# 3-Axis_Accelerometer.net
KiCad netlist of a schematic drawn in Altium Designer
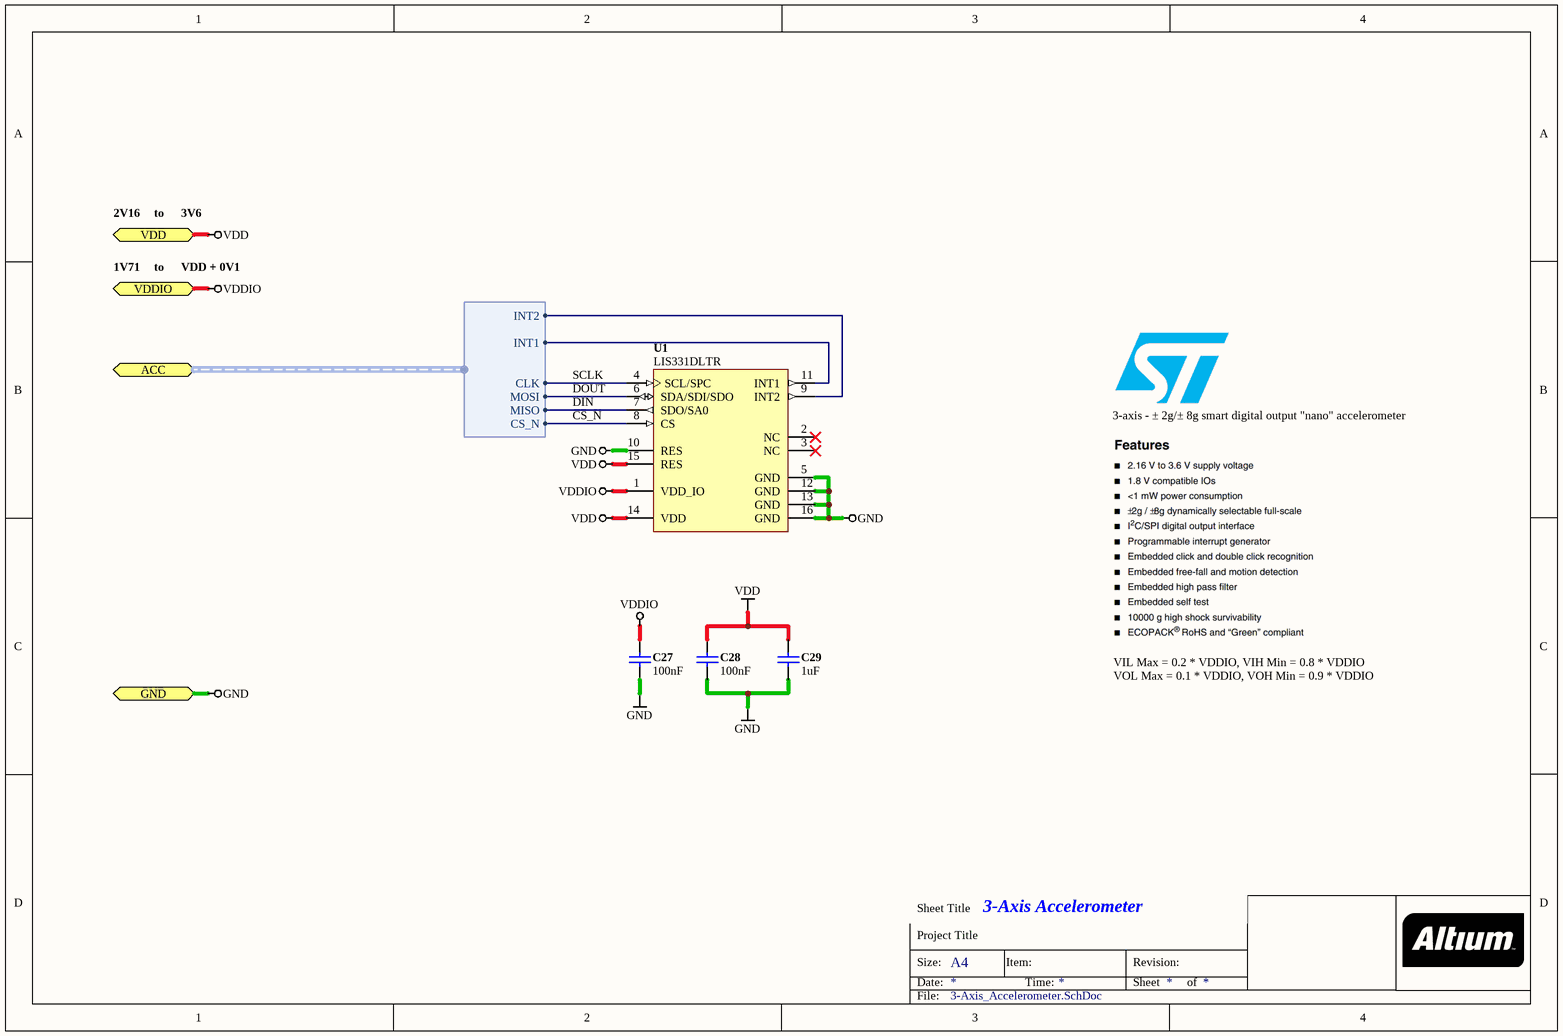
[diagram p0: 3-Axis_Accelerometer.SchDoc]

(export (version "E")
  (design (tool "Eeschema 10.0.6"))
  (components
    (comp (ref "C27")
      (value "100nF")
      (footprint "CAPC0402(1005)60_N")
      (description "CAP 100nF 16V ?0% 0402 (1005 Metric) Thickness 0.6mm SMD")
      (fields (field (name "TOLERANCE") "?0%") (field (name "Comment") "CAP 100nF 16V 0402(1005)"))
      (libsource (lib "Altium Content Vault") (part "CMP-1034-02069-1"))
    )
    (comp (ref "C28")
      (value "100nF")
      (footprint "CAPC0402(1005)60_N")
      (description "CAP 100nF 16V ?0% 0402 (1005 Metric) Thickness 0.6mm SMD")
      (fields (field (name "TOLERANCE") "?0%") (field (name "Comment") "CAP 100nF 16V 0402(1005)"))
      (libsource (lib "Altium Content Vault") (part "CMP-1034-02069-1"))
    )
    (comp (ref "C29")
      (value "1uF")
      (footprint "CAPC0402(1005)60_N")
      (description "CAP 1uF 16V ?0% 0402 (1005 Metric) Thickness 0.6mm SMD")
      (fields (field (name "TOLERANCE") "?0%") (field (name "Comment") "CAP 1uF 16V 0402(1005)"))
      (libsource (lib "Altium Content Vault") (part "CMP-1034-02119-1"))
    )
    (comp (ref "U1")
      (value "LIS331DLTR")
      (footprint "LGA16-3X3X1_L")
      (fields (field (name "MANUFACTURER") "STMicroelectronics"))
      (libsource (lib "Altium Content Vault") (part "CMP-0234-00061-2"))
    )
  )
  (nets
    (net (code "2") (name "/CS_N") (class "Default")
      (node (ref "U1") (pin "8") (pinfunction "CS_8") (pintype "input"))
    )
    (net (code "3") (name "/DIN") (class "Default")
      (node (ref "U1") (pin "7") (pinfunction "SDO/SA0_7") (pintype "output"))
    )
    (net (code "4") (name "/DOUT") (class "Default")
      (node (ref "U1") (pin "6") (pinfunction "SDA/SDI/SDO_6") (pintype "bidirectional"))
    )
    (net (code "5") (name "/INT1") (class "Default")
      (node (ref "U1") (pin "11") (pinfunction "INT1_11") (pintype "output"))
    )
    (net (code "6") (name "/INT2") (class "Default")
      (node (ref "U1") (pin "9") (pinfunction "INT2_9") (pintype "output"))
    )
    (net (code "7") (name "/SCLK") (class "Default")
      (node (ref "U1") (pin "4") (pinfunction "SCL/SPC_4") (pintype "input"))
    )
    (net (code "9") (name "GND") (class "Default")
      (node (ref "C27") (pin "2") (pinfunction "2_2") (pintype "passive"))
      (node (ref "C28") (pin "1") (pinfunction "1_1") (pintype "passive"))
      (node (ref "C29") (pin "2") (pinfunction "2_2") (pintype "passive"))
      (node (ref "U1") (pin "10") (pinfunction "RES_10") (pintype "passive"))
      (node (ref "U1") (pin "12") (pinfunction "GND_12") (pintype "power_in"))
      (node (ref "U1") (pin "13") (pinfunction "GND_13") (pintype "power_in"))
      (node (ref "U1") (pin "16") (pinfunction "GND_16") (pintype "power_in"))
      (node (ref "U1") (pin "5") (pinfunction "GND_5") (pintype "power_in"))
    )
    (net (code "10") (name "VDD") (class "Default")
      (node (ref "C28") (pin "2") (pinfunction "2_2") (pintype "passive"))
      (node (ref "C29") (pin "1") (pinfunction "1_1") (pintype "passive"))
      (node (ref "U1") (pin "14") (pinfunction "VDD_14") (pintype "power_in"))
      (node (ref "U1") (pin "15") (pinfunction "RES_15") (pintype "passive"))
    )
    (net (code "11") (name "VDDIO") (class "Default")
      (node (ref "C27") (pin "1") (pinfunction "1_1") (pintype "passive"))
      (node (ref "U1") (pin "1") (pinfunction "VDD_IO_1") (pintype "power_in"))
    )
    (net (code "12") (name "unconnected-(U1-NC-Pad2)") (class "Default")
      (node (ref "U1") (pin "2") (pinfunction "NC_2") (pintype "passive+no_connect"))
    )
    (net (code "13") (name "unconnected-(U1-NC-Pad3)") (class "Default")
      (node (ref "U1") (pin "3") (pinfunction "NC_3") (pintype "passive+no_connect"))
    )
  )
)
